# Adapter.net
KiCad netlist of a schematic drawn in Altium Designer
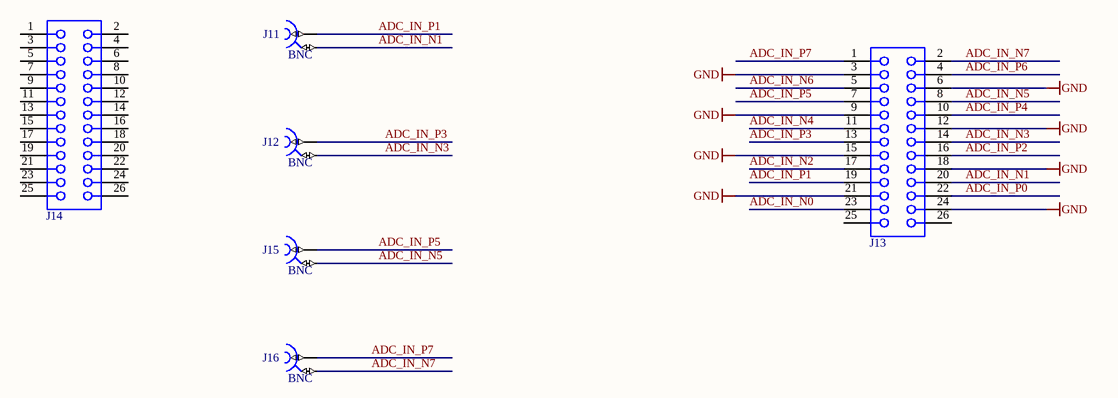
[diagram p0: Adapter.SchDoc]

(export (version "E")
  (design (tool "Eeschema 10.0.6"))
  (components
    (comp (ref "J11")
      (value "BNC")
      (footprint "MOLEX_73251-3150")
      (fields
        (field (name "PART NUMBER") "MOLEX_73251-3150")
        (field (name "MANUFACTURER") "MOLEX")
        (field (name "MANUFACTURER PART NUMBER") "73251-3150")
        (field (name "AUTHOR") "CERN DEM JLC")
      )
      (libsource (lib "DIOT_Sampler") (part "MOLEX_73251-3150"))
    )
    (comp (ref "J12")
      (value "BNC")
      (footprint "MOLEX_73251-3150")
      (fields
        (field (name "PART NUMBER") "MOLEX_73251-3150")
        (field (name "MANUFACTURER") "MOLEX")
        (field (name "MANUFACTURER PART NUMBER") "73251-3150")
        (field (name "AUTHOR") "CERN DEM JLC")
      )
      (libsource (lib "DIOT_Sampler") (part "MOLEX_73251-3150"))
    )
    (comp (ref "J13")
      (value "61032621821")
      (footprint "61032621821")
      (description "WR-PHD Socket Header, SMT, Vertical, pitch 2.54mm, 2 Row, 26P")
      (fields (field (name "MANUFACTURER") "Wurth Elektronik"))
      (libsource (lib "Altium_WR-PHD (rev24a)") (part "61032621821"))
    )
    (comp (ref "J14")
      (value "61302621821")
      (footprint "61302621821")
      (description "WR-PHD Socket Header, THT, Vertical, pitch 2.54mm, 2 Row, 26P")
      (fields (field (name "MANUFACTURER") "Wurth Elektronik"))
      (libsource (lib "Altium_WR-PHD (rev24a)") (part "61302621821"))
    )
    (comp (ref "J15")
      (value "BNC")
      (footprint "MOLEX_73251-3150")
      (fields
        (field (name "PART NUMBER") "MOLEX_73251-3150")
        (field (name "MANUFACTURER") "MOLEX")
        (field (name "MANUFACTURER PART NUMBER") "73251-3150")
        (field (name "AUTHOR") "CERN DEM JLC")
      )
      (libsource (lib "DIOT_Sampler") (part "MOLEX_73251-3150"))
    )
    (comp (ref "J16")
      (value "BNC")
      (footprint "MOLEX_73251-3150")
      (fields
        (field (name "PART NUMBER") "MOLEX_73251-3150")
        (field (name "MANUFACTURER") "MOLEX")
        (field (name "MANUFACTURER PART NUMBER") "73251-3150")
        (field (name "AUTHOR") "CERN DEM JLC")
      )
      (libsource (lib "DIOT_Sampler") (part "MOLEX_73251-3150"))
    )
  )
  (nets
    (net (code "1") (name "/ADC_IN_N0") (class "Default")
      (node (ref "J13") (pin "23") (pinfunction "23_23") (pintype "passive"))
    )
    (net (code "2") (name "/ADC_IN_N1") (class "Default")
      (node (ref "J11") (pin "2") (pinfunction "2_2") (pintype "bidirectional"))
      (node (ref "J13") (pin "20") (pinfunction "20_20") (pintype "passive"))
    )
    (net (code "3") (name "/ADC_IN_N2") (class "Default")
      (node (ref "J13") (pin "17") (pinfunction "17_17") (pintype "passive"))
    )
    (net (code "4") (name "/ADC_IN_N3") (class "Default")
      (node (ref "J12") (pin "2") (pinfunction "2_2") (pintype "bidirectional"))
      (node (ref "J13") (pin "14") (pinfunction "14_14") (pintype "passive"))
    )
    (net (code "5") (name "/ADC_IN_N4") (class "Default")
      (node (ref "J13") (pin "11") (pinfunction "11_11") (pintype "passive"))
    )
    (net (code "6") (name "/ADC_IN_N5") (class "Default")
      (node (ref "J13") (pin "8") (pinfunction "8_8") (pintype "passive"))
      (node (ref "J15") (pin "2") (pinfunction "2_2") (pintype "bidirectional"))
    )
    (net (code "7") (name "/ADC_IN_N6") (class "Default")
      (node (ref "J13") (pin "5") (pinfunction "5_5") (pintype "passive"))
    )
    (net (code "8") (name "/ADC_IN_N7") (class "Default")
      (node (ref "J13") (pin "2") (pinfunction "2_2") (pintype "passive"))
      (node (ref "J16") (pin "2") (pinfunction "2_2") (pintype "bidirectional"))
    )
    (net (code "9") (name "/ADC_IN_P0") (class "Default")
      (node (ref "J13") (pin "22") (pinfunction "22_22") (pintype "passive"))
    )
    (net (code "10") (name "/ADC_IN_P1") (class "Default")
      (node (ref "J11") (pin "1") (pinfunction "1_1") (pintype "bidirectional"))
      (node (ref "J13") (pin "19") (pinfunction "19_19") (pintype "passive"))
    )
    (net (code "11") (name "/ADC_IN_P2") (class "Default")
      (node (ref "J13") (pin "16") (pinfunction "16_16") (pintype "passive"))
    )
    (net (code "12") (name "/ADC_IN_P3") (class "Default")
      (node (ref "J12") (pin "1") (pinfunction "1_1") (pintype "bidirectional"))
      (node (ref "J13") (pin "13") (pinfunction "13_13") (pintype "passive"))
    )
    (net (code "13") (name "/ADC_IN_P4") (class "Default")
      (node (ref "J13") (pin "10") (pinfunction "10_10") (pintype "passive"))
    )
    (net (code "14") (name "/ADC_IN_P5") (class "Default")
      (node (ref "J13") (pin "7") (pinfunction "7_7") (pintype "passive"))
      (node (ref "J15") (pin "1") (pinfunction "1_1") (pintype "bidirectional"))
    )
    (net (code "15") (name "/ADC_IN_P6") (class "Default")
      (node (ref "J13") (pin "4") (pinfunction "4_4") (pintype "passive"))
    )
    (net (code "16") (name "/ADC_IN_P7") (class "Default")
      (node (ref "J13") (pin "1") (pinfunction "1_1") (pintype "passive"))
      (node (ref "J16") (pin "1") (pinfunction "1_1") (pintype "bidirectional"))
    )
    (net (code "17") (name "GND") (class "Default")
      (node (ref "J13") (pin "12") (pinfunction "12_12") (pintype "passive"))
      (node (ref "J13") (pin "15") (pinfunction "15_15") (pintype "passive"))
      (node (ref "J13") (pin "18") (pinfunction "18_18") (pintype "passive"))
      (node (ref "J13") (pin "21") (pinfunction "21_21") (pintype "passive"))
      (node (ref "J13") (pin "24") (pinfunction "24_24") (pintype "passive"))
      (node (ref "J13") (pin "3") (pinfunction "3_3") (pintype "passive"))
      (node (ref "J13") (pin "6") (pinfunction "6_6") (pintype "passive"))
      (node (ref "J13") (pin "9") (pinfunction "9_9") (pintype "passive"))
    )
    (net (code "18") (name "unconnected-(J13-Pad25)") (class "Default")
      (node (ref "J13") (pin "25") (pinfunction "25_25") (pintype "passive"))
    )
    (net (code "19") (name "unconnected-(J13-Pad26)") (class "Default")
      (node (ref "J13") (pin "26") (pinfunction "26_26") (pintype "passive"))
    )
    (net (code "20") (name "unconnected-(J14-Pad1)") (class "Default")
      (node (ref "J14") (pin "1") (pinfunction "1_1") (pintype "passive"))
    )
    (net (code "21") (name "unconnected-(J14-Pad2)") (class "Default")
      (node (ref "J14") (pin "2") (pinfunction "2_2") (pintype "passive"))
    )
    (net (code "22") (name "unconnected-(J14-Pad3)") (class "Default")
      (node (ref "J14") (pin "3") (pinfunction "3_3") (pintype "passive"))
    )
    (net (code "23") (name "unconnected-(J14-Pad4)") (class "Default")
      (node (ref "J14") (pin "4") (pinfunction "4_4") (pintype "passive"))
    )
    (net (code "24") (name "unconnected-(J14-Pad5)") (class "Default")
      (node (ref "J14") (pin "5") (pinfunction "5_5") (pintype "passive"))
    )
    (net (code "25") (name "unconnected-(J14-Pad6)") (class "Default")
      (node (ref "J14") (pin "6") (pinfunction "6_6") (pintype "passive"))
    )
    (net (code "26") (name "unconnected-(J14-Pad7)") (class "Default")
      (node (ref "J14") (pin "7") (pinfunction "7_7") (pintype "passive"))
    )
    (net (code "27") (name "unconnected-(J14-Pad8)") (class "Default")
      (node (ref "J14") (pin "8") (pinfunction "8_8") (pintype "passive"))
    )
    (net (code "28") (name "unconnected-(J14-Pad9)") (class "Default")
      (node (ref "J14") (pin "9") (pinfunction "9_9") (pintype "passive"))
    )
    (net (code "29") (name "unconnected-(J14-Pad10)") (class "Default")
      (node (ref "J14") (pin "10") (pinfunction "10_10") (pintype "passive"))
    )
    (net (code "30") (name "unconnected-(J14-Pad11)") (class "Default")
      (node (ref "J14") (pin "11") (pinfunction "11_11") (pintype "passive"))
    )
    (net (code "31") (name "unconnected-(J14-Pad12)") (class "Default")
      (node (ref "J14") (pin "12") (pinfunction "12_12") (pintype "passive"))
    )
    (net (code "32") (name "unconnected-(J14-Pad13)") (class "Default")
      (node (ref "J14") (pin "13") (pinfunction "13_13") (pintype "passive"))
    )
    (net (code "33") (name "unconnected-(J14-Pad14)") (class "Default")
      (node (ref "J14") (pin "14") (pinfunction "14_14") (pintype "passive"))
    )
    (net (code "34") (name "unconnected-(J14-Pad15)") (class "Default")
      (node (ref "J14") (pin "15") (pinfunction "15_15") (pintype "passive"))
    )
    (net (code "35") (name "unconnected-(J14-Pad16)") (class "Default")
      (node (ref "J14") (pin "16") (pinfunction "16_16") (pintype "passive"))
    )
    (net (code "36") (name "unconnected-(J14-Pad17)") (class "Default")
      (node (ref "J14") (pin "17") (pinfunction "17_17") (pintype "passive"))
    )
    (net (code "37") (name "unconnected-(J14-Pad18)") (class "Default")
      (node (ref "J14") (pin "18") (pinfunction "18_18") (pintype "passive"))
    )
    (net (code "38") (name "unconnected-(J14-Pad19)") (class "Default")
      (node (ref "J14") (pin "19") (pinfunction "19_19") (pintype "passive"))
    )
    (net (code "39") (name "unconnected-(J14-Pad20)") (class "Default")
      (node (ref "J14") (pin "20") (pinfunction "20_20") (pintype "passive"))
    )
    (net (code "40") (name "unconnected-(J14-Pad21)") (class "Default")
      (node (ref "J14") (pin "21") (pinfunction "21_21") (pintype "passive"))
    )
    (net (code "41") (name "unconnected-(J14-Pad22)") (class "Default")
      (node (ref "J14") (pin "22") (pinfunction "22_22") (pintype "passive"))
    )
    (net (code "42") (name "unconnected-(J14-Pad23)") (class "Default")
      (node (ref "J14") (pin "23") (pinfunction "23_23") (pintype "passive"))
    )
    (net (code "43") (name "unconnected-(J14-Pad24)") (class "Default")
      (node (ref "J14") (pin "24") (pinfunction "24_24") (pintype "passive"))
    )
    (net (code "44") (name "unconnected-(J14-Pad25)") (class "Default")
      (node (ref "J14") (pin "25") (pinfunction "25_25") (pintype "passive"))
    )
    (net (code "45") (name "unconnected-(J14-Pad26)") (class "Default")
      (node (ref "J14") (pin "26") (pinfunction "26_26") (pintype "passive"))
    )
  )
)
